# Encoder.net
KiCad netlist of a schematic drawn in Altium Designer
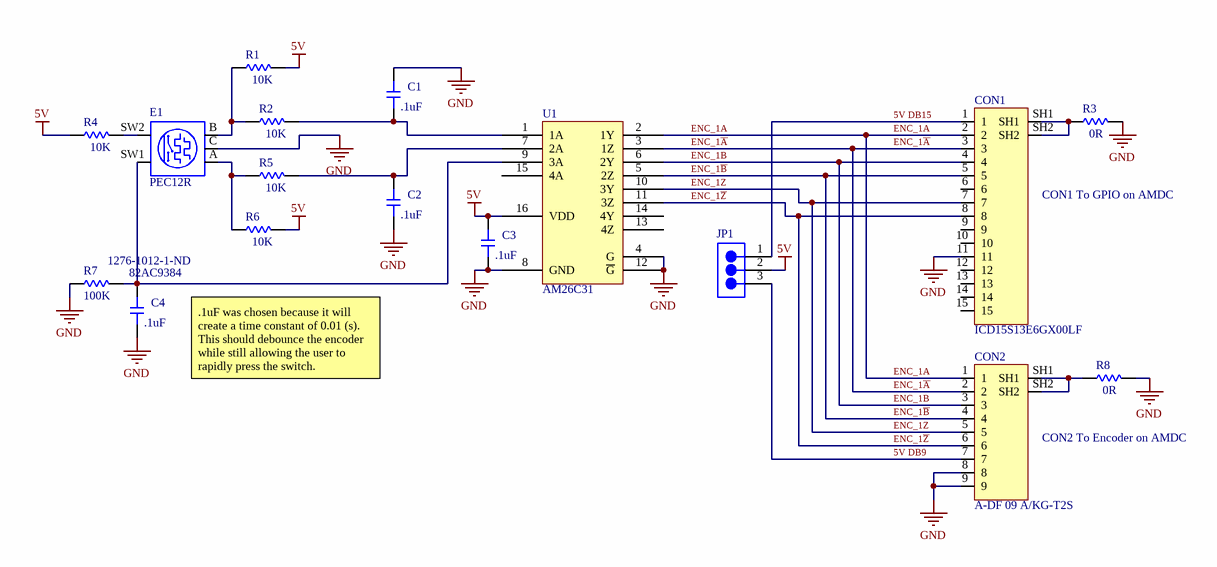
[diagram p0: Encoder.SchDoc]

(export (version "E")
  (design (tool "Eeschema 10.0.6"))
  (components
    (comp (ref "C1")
      (value "Capacitor .1uF")
      (footprint ".1uF Capacitor (0603-CAP)")
      (description "Capacitor")
      (libsource (lib "Encoder") (part "Capacitor .1uF"))
    )
    (comp (ref "C2")
      (value "Capacitor .1uF")
      (footprint ".1uF Capacitor (0603-CAP)")
      (description "Capacitor")
      (libsource (lib "Encoder") (part "Capacitor .1uF"))
    )
    (comp (ref "C3")
      (value "Capacitor .1uF")
      (footprint ".1uF Capacitor (0603-CAP)")
      (description "Capacitor")
      (libsource (lib "Encoder") (part "Capacitor .1uF"))
    )
    (comp (ref "C4")
      (value "Capacitor .1uF")
      (footprint ".1uF Capacitor (0603-CAP)")
      (description "Capacitor")
      (fields
        (field (name "SUPPLIER PART NUMBER 1") "82AC9384")
        (field (name "SUPPLIER PART NUMBER 2") "1276-1012-1-ND")
      )
      (libsource (lib "Encoder") (part "Capacitor .1uF"))
    )
    (comp (ref "CON1")
      (value "ICD15S13E6GX00LF")
      (footprint "ICD15S")
      (description "CONN D-SUB PLUG 15POS R/A SLDR")
      (libsource (lib "Encoder") (part "ICD15S13E6GX00LF"))
    )
    (comp (ref "CON2")
      (value "A-DF 09 A/KG-T2S")
      (footprint "DB9 Connector")
      (description "9 Position D-Sub Receptacle, Female Sockets Connector")
      (fields (field (name "MF") "Assmann WSW"))
      (libsource (lib "Encoder") (part "DB9 Connector A-DF_09_A/KG-T2S"))
    )
    (comp (ref "E1")
      (value "PEC12R")
      (footprint "Encoder")
      (libsource (lib "Encoder") (part "PEC12R-4220F-S0024"))
    )
    (comp (ref "JP1")
      (value "Jumper3")
      (footprint "PIN_HEADER_1X3")
      (libsource (lib "Encoder") (part "Jumper3"))
    )
    (comp (ref "R1")
      (value "Resistor")
      (footprint "10K Resistor (0603-RES)")
      (libsource (lib "Encoder") (part "Resistor 10K"))
    )
    (comp (ref "R2")
      (value "Resistor")
      (footprint "10K Resistor (0603-RES)")
      (libsource (lib "Encoder") (part "Resistor 10K"))
    )
    (comp (ref "R3")
      (value "Resistor")
      (footprint "0 Resistor (1206-RES)")
      (libsource (lib "Encoder") (part "Resistor 0R"))
    )
    (comp (ref "R4")
      (value "Resistor")
      (footprint "10K Resistor (0603-RES)")
      (libsource (lib "Encoder") (part "Resistor 10K"))
    )
    (comp (ref "R5")
      (value "Resistor")
      (footprint "10K Resistor (0603-RES)")
      (libsource (lib "Encoder") (part "Resistor 10K"))
    )
    (comp (ref "R6")
      (value "Resistor")
      (footprint "10K Resistor (0603-RES)")
      (libsource (lib "Encoder") (part "Resistor 10K"))
    )
    (comp (ref "R7")
      (value "Resistor")
      (footprint "100K Resistor (0603-RES)")
      (libsource (lib "Encoder") (part "Resistor 100K"))
    )
    (comp (ref "R8")
      (value "Resistor")
      (footprint "0 Resistor (1206-RES)")
      (libsource (lib "Encoder") (part "Resistor 0R"))
    )
    (comp (ref "U1")
      (value "AM26C31")
      (footprint "AM26C31")
      (description "IC DRIVER 4/0 16TSSOP")
      (libsource (lib "Encoder") (part "AM26C31"))
    )
  )
  (nets
    (net (code "1") (name "/5V DB9") (class "Default")
      (node (ref "CON2") (pin "7") (pinfunction "7_7") (pintype "passive"))
      (node (ref "JP1") (pin "3") (pinfunction "75_3") (pintype "passive"))
    )
    (net (code "2") (name "/5V DB15") (class "Default")
      (node (ref "CON1") (pin "1") (pinfunction "1_1") (pintype "passive"))
      (node (ref "JP1") (pin "1") (pinfunction "76_1") (pintype "passive"))
    )
    (net (code "3") (name "/ENC_1A") (class "Default")
      (node (ref "CON1") (pin "2") (pinfunction "2_2") (pintype "passive"))
      (node (ref "CON2") (pin "1") (pinfunction "1_1") (pintype "passive"))
      (node (ref "U1") (pin "2") (pinfunction "1Y_2") (pintype "passive"))
    )
    (net (code "4") (name "/ENC_1B") (class "Default")
      (node (ref "CON1") (pin "4") (pinfunction "4_4") (pintype "passive"))
      (node (ref "CON2") (pin "3") (pinfunction "3_3") (pintype "passive"))
      (node (ref "U1") (pin "6") (pinfunction "2Y_6") (pintype "passive"))
    )
    (net (code "5") (name "/ENC_1Z") (class "Default")
      (node (ref "CON1") (pin "7") (pinfunction "7_7") (pintype "passive"))
      (node (ref "CON2") (pin "5") (pinfunction "5_5") (pintype "passive"))
      (node (ref "U1") (pin "10") (pinfunction "3Y_10") (pintype "passive"))
    )
    (net (code "6") (name "/ENC_1~{A}") (class "Default")
      (node (ref "CON1") (pin "3") (pinfunction "3_3") (pintype "passive"))
      (node (ref "CON2") (pin "2") (pinfunction "2_2") (pintype "passive"))
      (node (ref "U1") (pin "3") (pinfunction "1Z_3") (pintype "passive"))
    )
    (net (code "7") (name "/ENC_1~{B}") (class "Default")
      (node (ref "CON1") (pin "5") (pinfunction "5_5") (pintype "passive"))
      (node (ref "CON2") (pin "4") (pinfunction "4_4") (pintype "passive"))
      (node (ref "U1") (pin "5") (pinfunction "2Z_5") (pintype "passive"))
    )
    (net (code "8") (name "/ENC_1~{Z}") (class "Default")
      (node (ref "CON1") (pin "8") (pinfunction "8_8") (pintype "passive"))
      (node (ref "CON2") (pin "6") (pinfunction "6_6") (pintype "passive"))
      (node (ref "U1") (pin "11") (pinfunction "3Z_11") (pintype "passive"))
    )
    (net (code "9") (name "5V") (class "Default")
      (node (ref "C3") (pin "1") (pinfunction "1_1") (pintype "passive"))
      (node (ref "JP1") (pin "2") (pinfunction "75_2") (pintype "passive"))
      (node (ref "R1") (pin "2") (pinfunction "2_2") (pintype "passive"))
      (node (ref "R4") (pin "1") (pinfunction "1_1") (pintype "passive"))
      (node (ref "R6") (pin "2") (pinfunction "2_2") (pintype "passive"))
      (node (ref "U1") (pin "16") (pinfunction "VDD_16") (pintype "passive"))
    )
    (net (code "10") (name "GND") (class "Default")
      (node (ref "C1") (pin "1") (pinfunction "1_1") (pintype "passive"))
      (node (ref "C2") (pin "2") (pinfunction "2_2") (pintype "passive"))
      (node (ref "C3") (pin "2") (pinfunction "2_2") (pintype "passive"))
      (node (ref "C4") (pin "2") (pinfunction "2_2") (pintype "passive"))
      (node (ref "CON1") (pin "11") (pinfunction "11_11") (pintype "passive"))
      (node (ref "CON2") (pin "8") (pinfunction "8_8") (pintype "passive"))
      (node (ref "CON2") (pin "9") (pinfunction "9_9") (pintype "passive"))
      (node (ref "E1") (pin "C") (pinfunction "C_C") (pintype "passive"))
      (node (ref "R3") (pin "2") (pinfunction "2_2") (pintype "passive"))
      (node (ref "R7") (pin "1") (pinfunction "1_1") (pintype "passive"))
      (node (ref "R8") (pin "2") (pinfunction "2_2") (pintype "passive"))
      (node (ref "U1") (pin "12") (pinfunction "~{G}_12") (pintype "passive"))
      (node (ref "U1") (pin "4") (pinfunction "G_4") (pintype "passive"))
      (node (ref "U1") (pin "8") (pinfunction "GND_8") (pintype "passive"))
    )
    (net (code "11") (name "Net-(CON1-PadSH1)") (class "Default")
      (node (ref "CON1") (pin "SH1") (pinfunction "SH1_SH1") (pintype "passive"))
      (node (ref "CON1") (pin "SH2") (pinfunction "SH2_SH2") (pintype "passive"))
      (node (ref "R3") (pin "1") (pinfunction "1_1") (pintype "passive"))
    )
    (net (code "12") (name "Net-(CON2-PadSH1)") (class "Default")
      (node (ref "CON2") (pin "SH1") (pinfunction "SH1_SH1") (pintype "passive"))
      (node (ref "CON2") (pin "SH2") (pinfunction "SH2_SH2") (pintype "passive"))
      (node (ref "R8") (pin "1") (pinfunction "1_1") (pintype "passive"))
    )
    (net (code "13") (name "Net-(E1-PadA)") (class "Default")
      (node (ref "E1") (pin "A") (pinfunction "A_A") (pintype "passive"))
      (node (ref "R5") (pin "1") (pinfunction "1_1") (pintype "passive"))
      (node (ref "R6") (pin "1") (pinfunction "1_1") (pintype "passive"))
    )
    (net (code "14") (name "Net-(E1-PadB)") (class "Default")
      (node (ref "E1") (pin "B") (pinfunction "B_B") (pintype "passive"))
      (node (ref "R1") (pin "1") (pinfunction "1_1") (pintype "passive"))
      (node (ref "R2") (pin "1") (pinfunction "1_1") (pintype "passive"))
    )
    (net (code "15") (name "Net-(E1-PadSW2)") (class "Default")
      (node (ref "E1") (pin "SW2") (pinfunction "SW2_SW2") (pintype "passive"))
      (node (ref "R4") (pin "2") (pinfunction "2_2") (pintype "passive"))
    )
    (net (code "16") (name "Net-(U1-1A)") (class "Default")
      (node (ref "C1") (pin "2") (pinfunction "2_2") (pintype "passive"))
      (node (ref "R2") (pin "2") (pinfunction "2_2") (pintype "passive"))
      (node (ref "U1") (pin "1") (pinfunction "1A_1") (pintype "passive"))
    )
    (net (code "17") (name "Net-(U1-2A)") (class "Default")
      (node (ref "C2") (pin "1") (pinfunction "1_1") (pintype "passive"))
      (node (ref "R5") (pin "2") (pinfunction "2_2") (pintype "passive"))
      (node (ref "U1") (pin "7") (pinfunction "2A_7") (pintype "passive"))
    )
    (net (code "18") (name "Net-(U1-3A)") (class "Default")
      (node (ref "C4") (pin "1") (pinfunction "1_1") (pintype "passive"))
      (node (ref "E1") (pin "SW1") (pinfunction "SW1_SW1") (pintype "passive"))
      (node (ref "R7") (pin "2") (pinfunction "2_2") (pintype "passive"))
      (node (ref "U1") (pin "9") (pinfunction "3A_9") (pintype "passive"))
    )
    (net (code "19") (name "unconnected-(CON1-Pad6)") (class "Default")
      (node (ref "CON1") (pin "6") (pinfunction "6_6") (pintype "passive"))
    )
    (net (code "20") (name "unconnected-(CON1-Pad9)") (class "Default")
      (node (ref "CON1") (pin "9") (pinfunction "9_9") (pintype "passive"))
    )
    (net (code "21") (name "unconnected-(CON1-Pad10)") (class "Default")
      (node (ref "CON1") (pin "10") (pinfunction "10_10") (pintype "passive"))
    )
    (net (code "22") (name "unconnected-(CON1-Pad12)") (class "Default")
      (node (ref "CON1") (pin "12") (pinfunction "12_12") (pintype "passive"))
    )
    (net (code "23") (name "unconnected-(CON1-Pad13)") (class "Default")
      (node (ref "CON1") (pin "13") (pinfunction "13_13") (pintype "passive"))
    )
    (net (code "24") (name "unconnected-(CON1-Pad14)") (class "Default")
      (node (ref "CON1") (pin "14") (pinfunction "14_14") (pintype "passive"))
    )
    (net (code "25") (name "unconnected-(CON1-Pad15)") (class "Default")
      (node (ref "CON1") (pin "15") (pinfunction "15_15") (pintype "passive"))
    )
    (net (code "26") (name "unconnected-(U1-4A-Pad15)") (class "Default")
      (node (ref "U1") (pin "15") (pinfunction "4A_15") (pintype "passive"))
    )
    (net (code "27") (name "unconnected-(U1-4Y-Pad14)") (class "Default")
      (node (ref "U1") (pin "14") (pinfunction "4Y_14") (pintype "passive"))
    )
    (net (code "28") (name "unconnected-(U1-4Z-Pad13)") (class "Default")
      (node (ref "U1") (pin "13") (pinfunction "4Z_13") (pintype "passive"))
    )
  )
)
